# Display_Driver.net
KiCad netlist of a schematic drawn in Altium Designer
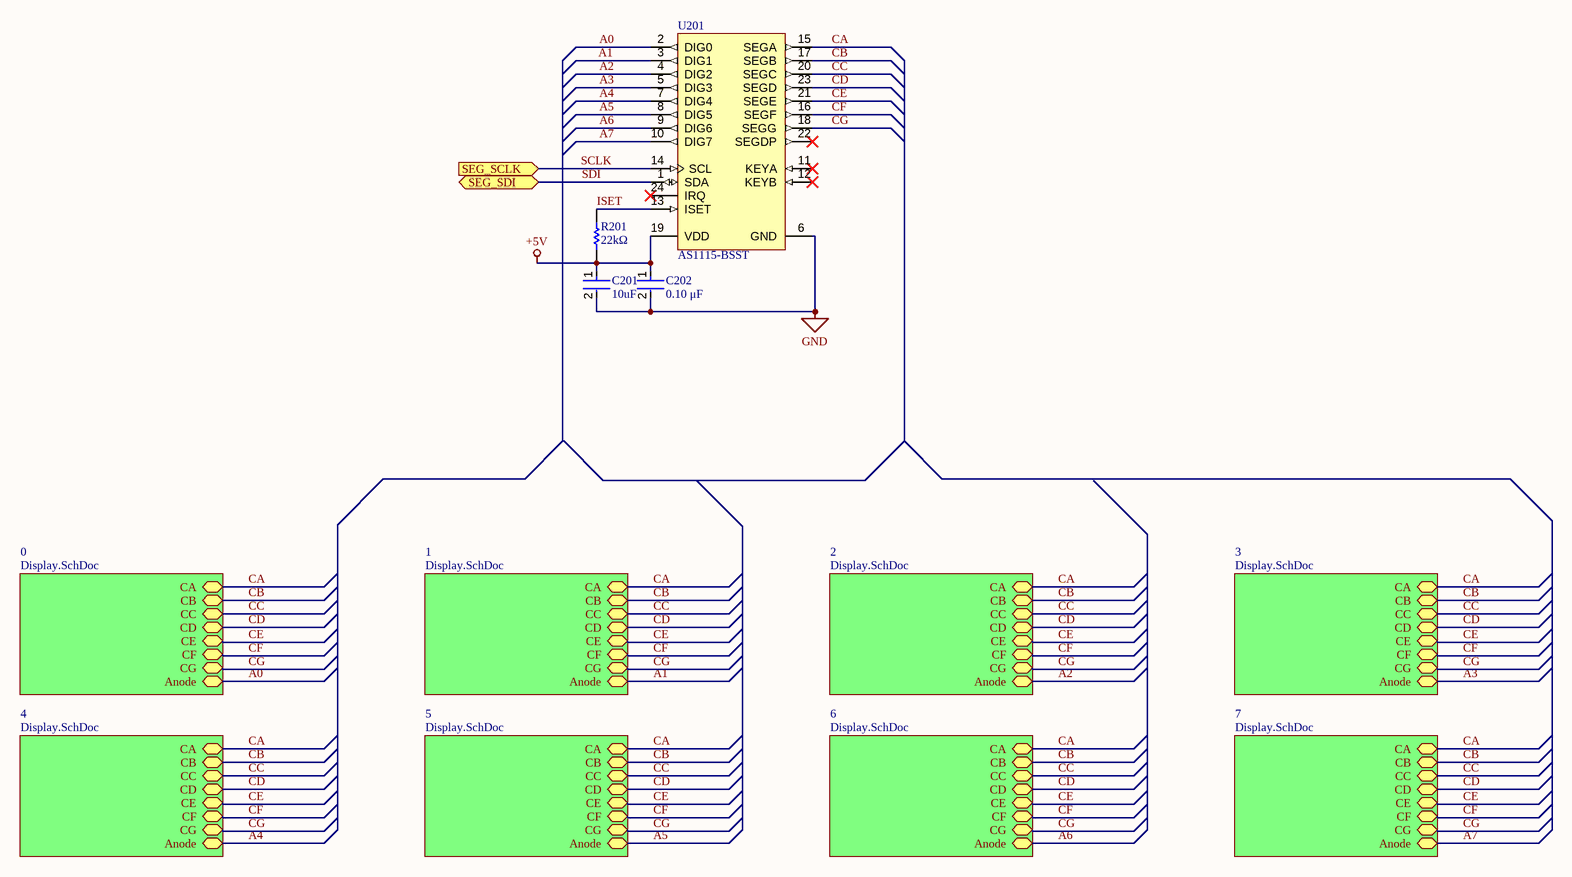
[diagram p0: Display Driver.SchDoc]

(export (version "E")
  (design (tool "Eeschema 10.0.6"))
  (components
    (comp (ref "C201")
      (value "C1206C106K4RACAUTO")
      (footprint "FP-C1206C-EH-MFG")
      (description "CAP CER 10UF 16V X7R 1206")
      (fields
        (field (name "MANUFACTURER") "Kemet")
        (field (name "OCTOPART") "https://octopart.com/c1206c106k4racauto-kemet-20072893")
        (field (name "CAPACITANCE") "10uF")
      )
      (libsource (lib "Altium Content Vault") (part "b4654b650e69147ec39a6b967a45e02"))
    )
    (comp (ref "C202")
      (value "C0603C104K5RACAUTO")
      (footprint "FP-C0603C-CF-MFG")
      (description "CAP CER 0.1UF 50V X7R 0603")
      (fields
        (field (name "MANUFACTURER") "KEMET")
        (field (name "OCTOPART") "https://octopart.com/c0603c104k5racauto-kemet-12563741")
        (field (name "CAPACITANCE") "0.10 μF")
      )
      (libsource (lib "Altium Content Vault") (part "b4654b650e69147ec39a6b967a45e02"))
    )
    (comp (ref "R201")
      (value "RC0603FR-0722KL")
      (footprint "RESC1608X55X25LL10T15")
      (description "Chip Resistor, 22 KOhm, +/- 1%, 0.1 W, -55 to 155 degC, 0603 (1608 Metric), RoHS, Tape and Reel")
      (fields (field (name "TOLERANCE") "10%") (field (name "RESISTANCE") "22kΩ"))
      (libsource (lib "Altium Content Vault") (part "RES-2"))
    )
    (comp (ref "U201")
      (value "AS1115-BSST")
      (footprint "AMS-QSOP-24-8645X3900DE_N")
      (description "64 LED + 16 Keys User Interface LED Driver, I2C Interface, 2.7 to 5.5 V, QSOP-24, Pb-Free, Reel")
      (fields (field (name "MANUFACTURER") "AMS"))
      (libsource (lib "Altium Content Vault") (part "AMS-AS1115-QSOP-24"))
    )
  )
  (nets
    (net (code "1") (name "+5V") (class "Default")
      (node (ref "C201") (pin "1") (pinfunction "1_1") (pintype "passive"))
      (node (ref "C202") (pin "1") (pinfunction "1_1") (pintype "passive"))
      (node (ref "R201") (pin "1") (pinfunction "1_1") (pintype "passive"))
      (node (ref "U201") (pin "19") (pinfunction "VDD_19") (pintype "power_in"))
    )
    (net (code "2") (name "/A0") (class "Default")
      (node (ref "U201") (pin "2") (pinfunction "DIG0_2") (pintype "output"))
    )
    (net (code "3") (name "/A1") (class "Default")
      (node (ref "U201") (pin "3") (pinfunction "DIG1_3") (pintype "output"))
    )
    (net (code "4") (name "/A2") (class "Default")
      (node (ref "U201") (pin "4") (pinfunction "DIG2_4") (pintype "output"))
    )
    (net (code "5") (name "/A3") (class "Default")
      (node (ref "U201") (pin "5") (pinfunction "DIG3_5") (pintype "output"))
    )
    (net (code "6") (name "/A4") (class "Default")
      (node (ref "U201") (pin "7") (pinfunction "DIG4_7") (pintype "output"))
    )
    (net (code "7") (name "/A5") (class "Default")
      (node (ref "U201") (pin "8") (pinfunction "DIG5_8") (pintype "output"))
    )
    (net (code "8") (name "/A6") (class "Default")
      (node (ref "U201") (pin "9") (pinfunction "DIG6_9") (pintype "output"))
    )
    (net (code "9") (name "/A7") (class "Default")
      (node (ref "U201") (pin "10") (pinfunction "DIG7_10") (pintype "output"))
    )
    (net (code "10") (name "/CA") (class "Default")
      (node (ref "U201") (pin "15") (pinfunction "SEGA_15") (pintype "output"))
    )
    (net (code "11") (name "/CB") (class "Default")
      (node (ref "U201") (pin "17") (pinfunction "SEGB_17") (pintype "output"))
    )
    (net (code "12") (name "/CC") (class "Default")
      (node (ref "U201") (pin "20") (pinfunction "SEGC_20") (pintype "output"))
    )
    (net (code "13") (name "/CD") (class "Default")
      (node (ref "U201") (pin "23") (pinfunction "SEGD_23") (pintype "output"))
    )
    (net (code "14") (name "/CE") (class "Default")
      (node (ref "U201") (pin "21") (pinfunction "SEGE_21") (pintype "output"))
    )
    (net (code "15") (name "/CF") (class "Default")
      (node (ref "U201") (pin "16") (pinfunction "SEGF_16") (pintype "output"))
    )
    (net (code "16") (name "/CG") (class "Default")
      (node (ref "U201") (pin "18") (pinfunction "SEGG_18") (pintype "output"))
    )
    (net (code "17") (name "/ISET") (class "Default")
      (node (ref "R201") (pin "2") (pinfunction "2_2") (pintype "passive"))
      (node (ref "U201") (pin "13") (pinfunction "ISET_13") (pintype "input"))
    )
    (net (code "18") (name "/SCLK") (class "Default")
      (node (ref "U201") (pin "14") (pinfunction "SCL_14") (pintype "input"))
    )
    (net (code "19") (name "/SDI") (class "Default")
      (node (ref "U201") (pin "1") (pinfunction "SDA_1") (pintype "bidirectional"))
    )
    (net (code "20") (name "GND") (class "Default")
      (node (ref "C201") (pin "2") (pinfunction "2_2") (pintype "passive"))
      (node (ref "C202") (pin "2") (pinfunction "2_2") (pintype "passive"))
      (node (ref "U201") (pin "6") (pinfunction "GND_6") (pintype "power_in"))
    )
    (net (code "21") (name "unconnected-(U201-IRQ-Pad24)") (class "Default")
      (node (ref "U201") (pin "24") (pinfunction "IRQ_24") (pintype "tri_state+no_connect"))
    )
    (net (code "22") (name "unconnected-(U201-KEYA-Pad11)") (class "Default")
      (node (ref "U201") (pin "11") (pinfunction "KEYA_11") (pintype "input+no_connect"))
    )
    (net (code "23") (name "unconnected-(U201-KEYB-Pad12)") (class "Default")
      (node (ref "U201") (pin "12") (pinfunction "KEYB_12") (pintype "input+no_connect"))
    )
    (net (code "24") (name "unconnected-(U201-SEGDP-Pad22)") (class "Default")
      (node (ref "U201") (pin "22") (pinfunction "SEGDP_22") (pintype "output+no_connect"))
    )
  )
)
